# Dev-PCB.net
KiCad netlist of a schematic drawn in EAGLE
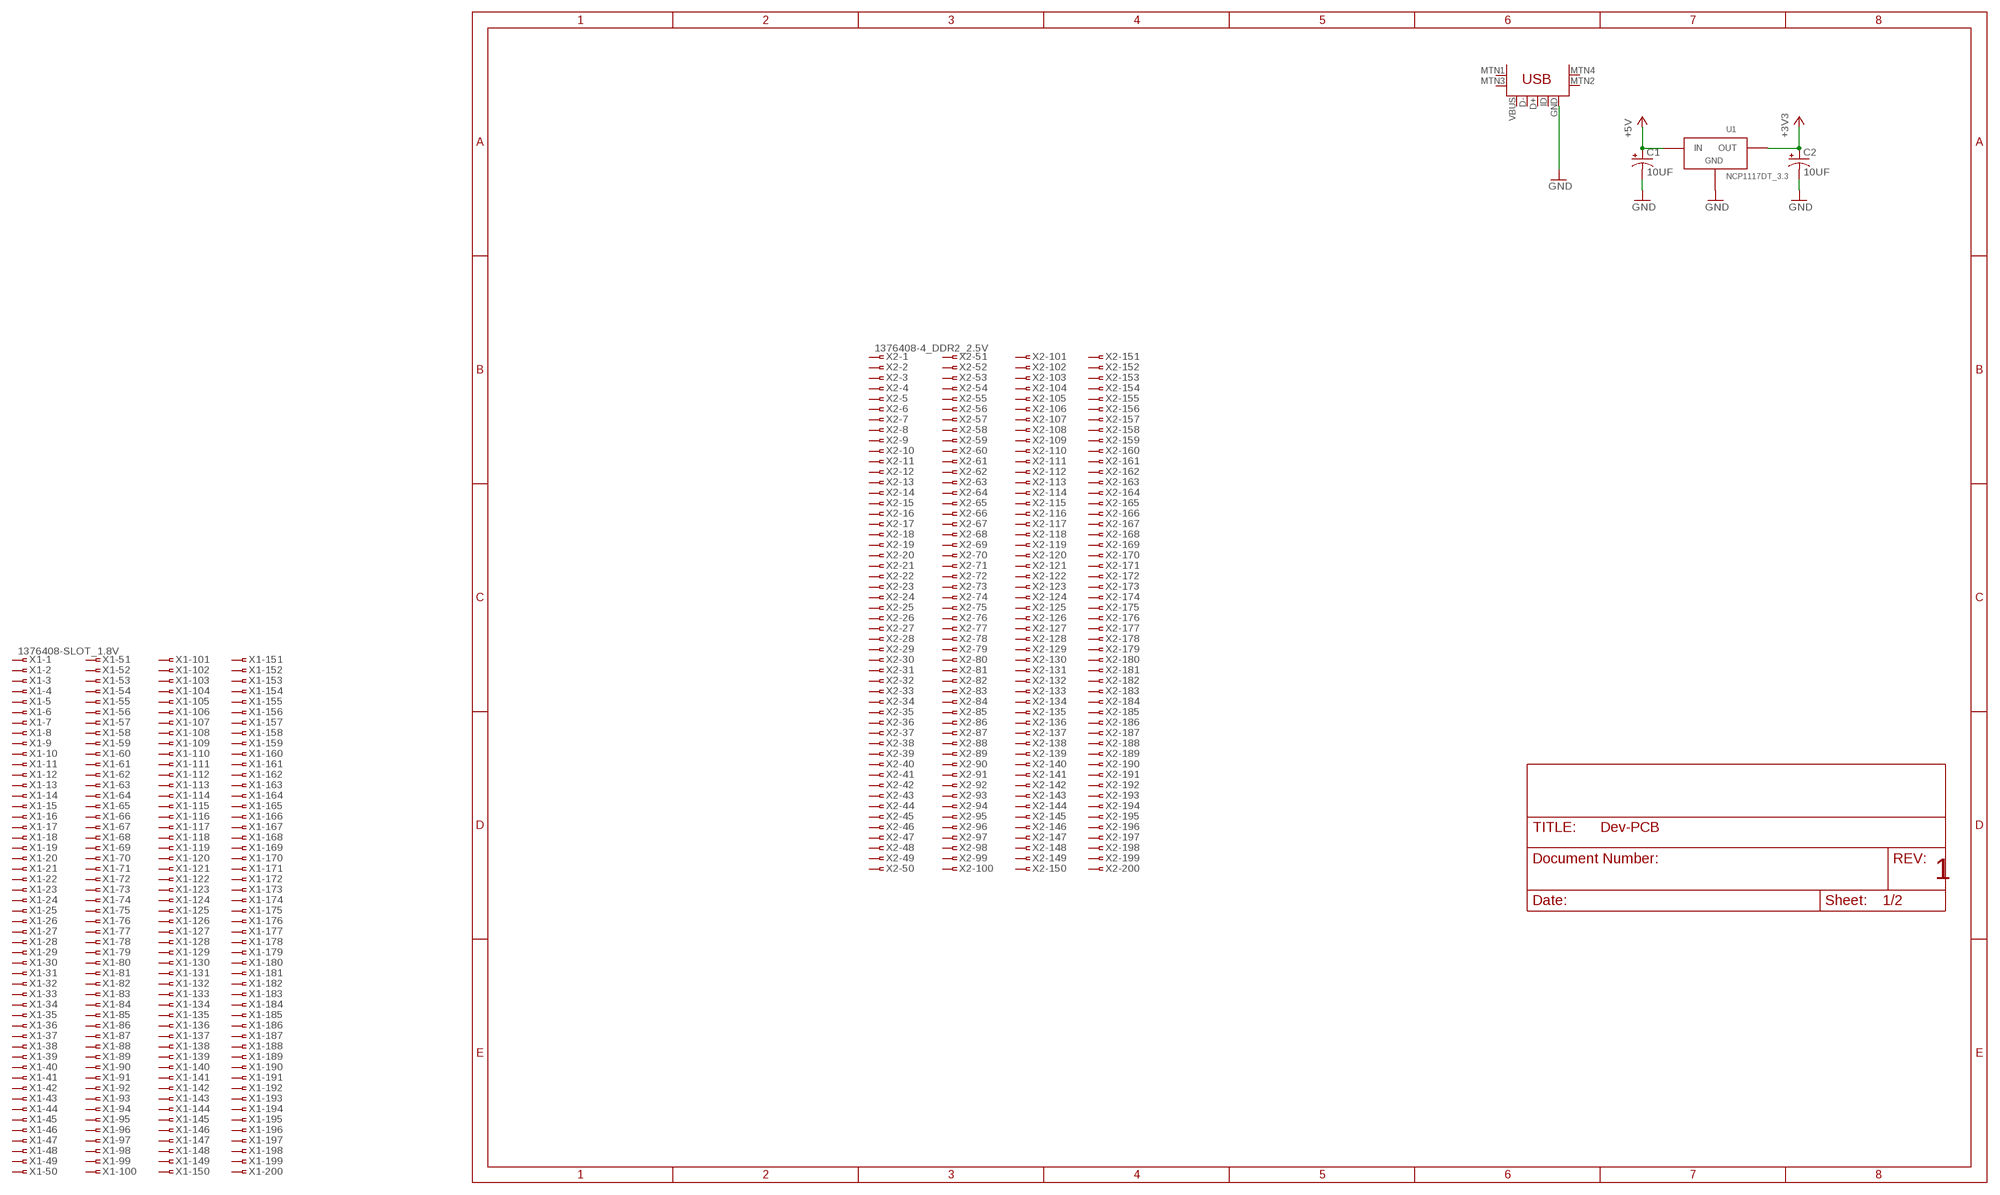
[diagram p0: schematic, sheet 1]

(export (version "E")
  (design (tool "Eeschema 10.0.6"))
  (components
    (comp (ref "C1")
      (value "10UF")
      (footprint "eagle-import:EIA3216-16V")
      (fields (field (name "PARTNO") "T491A106M016AT"))
      (libsource (lib "eagle-import") (part "CAP-POL_10UF_16V"))
    )
    (comp (ref "C2")
      (value "10UF")
      (footprint "eagle-import:EIA3216-16V")
      (fields (field (name "PARTNO") "T491A106M016AT"))
      (libsource (lib "eagle-import") (part "CAP-POL_10UF_16V"))
    )
    (comp (ref "U$1")
      (value "USB-MINIB-5PIN")
      (footprint "eagle-import:USB-MINIB")
      (libsource (lib "eagle-import") (part "USB-MINIB-5PIN"))
    )
    (comp (ref "U1")
      (value "NCP1117DT_3.3")
      (footprint "eagle-import:DPAK")
      (fields (field (name "PARTNO") "NCP1117DT33RKG"))
      (libsource (lib "eagle-import") (part "NCP1117DT_3.3"))
    )
    (comp (ref "X1")
      (value "1376408-SLOT_1.8V")
      (footprint "eagle-import:SLOT-1376408-1_1.8V")
      (libsource (lib "eagle-import") (part "1376408-SLOT_1.8V"))
    )
    (comp (ref "X2")
      (value "1376408-4_DDR2_2.5V")
      (footprint "eagle-import:1-1376408-4")
      (libsource (lib "eagle-import") (part "1376408-4_DDR2_2.5V"))
    )
  )
  (nets
    (net (code "1") (name "+3V3") (class "Default")
      (node (ref "C2") (pin "A") (pinfunction "+_A") (pintype "passive"))
      (node (ref "U1") (pin "2") (pinfunction "OUT_2") (pintype "bidirectional"))
    )
    (net (code "2") (name "+5V") (class "Default")
      (node (ref "C1") (pin "A") (pinfunction "+_A") (pintype "passive"))
      (node (ref "U1") (pin "3") (pinfunction "IN_3") (pintype "bidirectional"))
    )
    (net (code "3") (name "GND") (class "Default")
      (node (ref "C1") (pin "C") (pinfunction "+1_C") (pintype "passive"))
      (node (ref "C2") (pin "C") (pinfunction "+1_C") (pintype "passive"))
      (node (ref "U$1") (pin "GND") (pinfunction "GND_GND") (pintype "bidirectional"))
      (node (ref "U1") (pin "1") (pinfunction "GND_1") (pintype "bidirectional"))
    )
    (net (code "4") (name "unconnected-(U$1-MTN1-PadMTN3)") (class "Default")
      (node (ref "U$1") (pin "MTN3") (pinfunction "MTN1_MTN3") (pintype "bidirectional"))
    )
    (net (code "5") (name "unconnected-(U$1-MTN2-PadMTN1)") (class "Default")
      (node (ref "U$1") (pin "MTN1") (pinfunction "MTN2_MTN1") (pintype "bidirectional"))
    )
    (net (code "6") (name "unconnected-(U$1-MTN3-PadMTN2)") (class "Default")
      (node (ref "U$1") (pin "MTN2") (pinfunction "MTN3_MTN2") (pintype "bidirectional"))
    )
    (net (code "7") (name "unconnected-(U$1-PadD+)") (class "Default")
      (node (ref "U$1") (pin "D+") (pinfunction "D+_D+") (pintype "bidirectional"))
    )
    (net (code "8") (name "unconnected-(U$1-PadD-)") (class "Default")
      (node (ref "U$1") (pin "D-") (pinfunction "D-_D-") (pintype "bidirectional"))
    )
    (net (code "9") (name "unconnected-(U$1-PadID)") (class "Default")
      (node (ref "U$1") (pin "ID") (pinfunction "ID_ID") (pintype "bidirectional"))
    )
    (net (code "10") (name "unconnected-(U$1-PadMTN4)") (class "Default")
      (node (ref "U$1") (pin "MTN4") (pinfunction "MTN4_MTN4") (pintype "bidirectional"))
    )
    (net (code "11") (name "unconnected-(U$1-PadVBUS)") (class "Default")
      (node (ref "U$1") (pin "VBUS") (pinfunction "VBUS_VBUS") (pintype "bidirectional"))
    )
    (net (code "12") (name "unconnected-(X1-Pad1)") (class "Default")
      (node (ref "X1") (pin "1") (pinfunction "1_1") (pintype "passive"))
    )
    (net (code "13") (name "unconnected-(X1AA-1-Pad122)") (class "Default")
      (node (ref "X1") (pin "122") (pinfunction "1_122") (pintype "passive"))
    )
    (net (code "14") (name "unconnected-(X1AB-1-Pad123)") (class "Default")
      (node (ref "X1") (pin "123") (pinfunction "1_123") (pintype "passive"))
    )
    (net (code "15") (name "unconnected-(X1AC-1-Pad124)") (class "Default")
      (node (ref "X1") (pin "124") (pinfunction "1_124") (pintype "passive"))
    )
    (net (code "16") (name "unconnected-(X1AD-1-Pad125)") (class "Default")
      (node (ref "X1") (pin "125") (pinfunction "1_125") (pintype "passive"))
    )
    (net (code "17") (name "unconnected-(X1AE-1-Pad126)") (class "Default")
      (node (ref "X1") (pin "126") (pinfunction "1_126") (pintype "passive"))
    )
    (net (code "18") (name "unconnected-(X1AF-1-Pad127)") (class "Default")
      (node (ref "X1") (pin "127") (pinfunction "1_127") (pintype "passive"))
    )
    (net (code "19") (name "unconnected-(X1AG-1-Pad128)") (class "Default")
      (node (ref "X1") (pin "128") (pinfunction "1_128") (pintype "passive"))
    )
    (net (code "20") (name "unconnected-(X1AH-1-Pad129)") (class "Default")
      (node (ref "X1") (pin "129") (pinfunction "1_129") (pintype "passive"))
    )
    (net (code "21") (name "unconnected-(X1AI-1-Pad13)") (class "Default")
      (node (ref "X1") (pin "13") (pinfunction "1_13") (pintype "passive"))
    )
    (net (code "22") (name "unconnected-(X1AJ-1-Pad130)") (class "Default")
      (node (ref "X1") (pin "130") (pinfunction "1_130") (pintype "passive"))
    )
    (net (code "23") (name "unconnected-(X1AK-1-Pad131)") (class "Default")
      (node (ref "X1") (pin "131") (pinfunction "1_131") (pintype "passive"))
    )
    (net (code "24") (name "unconnected-(X1AL-1-Pad132)") (class "Default")
      (node (ref "X1") (pin "132") (pinfunction "1_132") (pintype "passive"))
    )
    (net (code "25") (name "unconnected-(X1AM-1-Pad133)") (class "Default")
      (node (ref "X1") (pin "133") (pinfunction "1_133") (pintype "passive"))
    )
    (net (code "26") (name "unconnected-(X1AN-1-Pad134)") (class "Default")
      (node (ref "X1") (pin "134") (pinfunction "1_134") (pintype "passive"))
    )
    (net (code "27") (name "unconnected-(X1AO-1-Pad135)") (class "Default")
      (node (ref "X1") (pin "135") (pinfunction "1_135") (pintype "passive"))
    )
    (net (code "28") (name "unconnected-(X1AP-1-Pad136)") (class "Default")
      (node (ref "X1") (pin "136") (pinfunction "1_136") (pintype "passive"))
    )
    (net (code "29") (name "unconnected-(X1AQ-1-Pad137)") (class "Default")
      (node (ref "X1") (pin "137") (pinfunction "1_137") (pintype "passive"))
    )
    (net (code "30") (name "unconnected-(X1AR-1-Pad138)") (class "Default")
      (node (ref "X1") (pin "138") (pinfunction "1_138") (pintype "passive"))
    )
    (net (code "31") (name "unconnected-(X1AS-1-Pad139)") (class "Default")
      (node (ref "X1") (pin "139") (pinfunction "1_139") (pintype "passive"))
    )
    (net (code "32") (name "unconnected-(X1AT-1-Pad14)") (class "Default")
      (node (ref "X1") (pin "14") (pinfunction "1_14") (pintype "passive"))
    )
    (net (code "33") (name "unconnected-(X1AU-1-Pad140)") (class "Default")
      (node (ref "X1") (pin "140") (pinfunction "1_140") (pintype "passive"))
    )
    (net (code "34") (name "unconnected-(X1AV-1-Pad141)") (class "Default")
      (node (ref "X1") (pin "141") (pinfunction "1_141") (pintype "passive"))
    )
    (net (code "35") (name "unconnected-(X1AW-1-Pad142)") (class "Default")
      (node (ref "X1") (pin "142") (pinfunction "1_142") (pintype "passive"))
    )
    (net (code "36") (name "unconnected-(X1AX-1-Pad143)") (class "Default")
      (node (ref "X1") (pin "143") (pinfunction "1_143") (pintype "passive"))
    )
    (net (code "37") (name "unconnected-(X1AY-1-Pad144)") (class "Default")
      (node (ref "X1") (pin "144") (pinfunction "1_144") (pintype "passive"))
    )
    (net (code "38") (name "unconnected-(X1AZ-1-Pad145)") (class "Default")
      (node (ref "X1") (pin "145") (pinfunction "1_145") (pintype "passive"))
    )
    (net (code "39") (name "unconnected-(X1B-1-Pad10)") (class "Default")
      (node (ref "X1") (pin "10") (pinfunction "1_10") (pintype "passive"))
    )
    (net (code "40") (name "unconnected-(X1BA-1-Pad146)") (class "Default")
      (node (ref "X1") (pin "146") (pinfunction "1_146") (pintype "passive"))
    )
    (net (code "41") (name "unconnected-(X1BB-1-Pad147)") (class "Default")
      (node (ref "X1") (pin "147") (pinfunction "1_147") (pintype "passive"))
    )
    (net (code "42") (name "unconnected-(X1BC-1-Pad148)") (class "Default")
      (node (ref "X1") (pin "148") (pinfunction "1_148") (pintype "passive"))
    )
    (net (code "43") (name "unconnected-(X1BD-1-Pad149)") (class "Default")
      (node (ref "X1") (pin "149") (pinfunction "1_149") (pintype "passive"))
    )
    (net (code "44") (name "unconnected-(X1BE-1-Pad15)") (class "Default")
      (node (ref "X1") (pin "15") (pinfunction "1_15") (pintype "passive"))
    )
    (net (code "45") (name "unconnected-(X1BF-1-Pad150)") (class "Default")
      (node (ref "X1") (pin "150") (pinfunction "1_150") (pintype "passive"))
    )
    (net (code "46") (name "unconnected-(X1BG-1-Pad151)") (class "Default")
      (node (ref "X1") (pin "151") (pinfunction "1_151") (pintype "passive"))
    )
    (net (code "47") (name "unconnected-(X1BH-1-Pad152)") (class "Default")
      (node (ref "X1") (pin "152") (pinfunction "1_152") (pintype "passive"))
    )
    (net (code "48") (name "unconnected-(X1BI-1-Pad153)") (class "Default")
      (node (ref "X1") (pin "153") (pinfunction "1_153") (pintype "passive"))
    )
    (net (code "49") (name "unconnected-(X1BJ-1-Pad154)") (class "Default")
      (node (ref "X1") (pin "154") (pinfunction "1_154") (pintype "passive"))
    )
    (net (code "50") (name "unconnected-(X1BK-1-Pad155)") (class "Default")
      (node (ref "X1") (pin "155") (pinfunction "1_155") (pintype "passive"))
    )
    (net (code "51") (name "unconnected-(X1BL-1-Pad156)") (class "Default")
      (node (ref "X1") (pin "156") (pinfunction "1_156") (pintype "passive"))
    )
    (net (code "52") (name "unconnected-(X1BM-1-Pad157)") (class "Default")
      (node (ref "X1") (pin "157") (pinfunction "1_157") (pintype "passive"))
    )
    (net (code "53") (name "unconnected-(X1BN-1-Pad158)") (class "Default")
      (node (ref "X1") (pin "158") (pinfunction "1_158") (pintype "passive"))
    )
    (net (code "54") (name "unconnected-(X1BO-1-Pad159)") (class "Default")
      (node (ref "X1") (pin "159") (pinfunction "1_159") (pintype "passive"))
    )
    (net (code "55") (name "unconnected-(X1BP-1-Pad16)") (class "Default")
      (node (ref "X1") (pin "16") (pinfunction "1_16") (pintype "passive"))
    )
    (net (code "56") (name "unconnected-(X1BQ-1-Pad160)") (class "Default")
      (node (ref "X1") (pin "160") (pinfunction "1_160") (pintype "passive"))
    )
    (net (code "57") (name "unconnected-(X1BR-1-Pad161)") (class "Default")
      (node (ref "X1") (pin "161") (pinfunction "1_161") (pintype "passive"))
    )
    (net (code "58") (name "unconnected-(X1BS-1-Pad162)") (class "Default")
      (node (ref "X1") (pin "162") (pinfunction "1_162") (pintype "passive"))
    )
    (net (code "59") (name "unconnected-(X1BT-1-Pad163)") (class "Default")
      (node (ref "X1") (pin "163") (pinfunction "1_163") (pintype "passive"))
    )
    (net (code "60") (name "unconnected-(X1BU-1-Pad164)") (class "Default")
      (node (ref "X1") (pin "164") (pinfunction "1_164") (pintype "passive"))
    )
    (net (code "61") (name "unconnected-(X1BV-1-Pad165)") (class "Default")
      (node (ref "X1") (pin "165") (pinfunction "1_165") (pintype "passive"))
    )
    (net (code "62") (name "unconnected-(X1BW-1-Pad166)") (class "Default")
      (node (ref "X1") (pin "166") (pinfunction "1_166") (pintype "passive"))
    )
    (net (code "63") (name "unconnected-(X1BX-1-Pad167)") (class "Default")
      (node (ref "X1") (pin "167") (pinfunction "1_167") (pintype "passive"))
    )
    (net (code "64") (name "unconnected-(X1BY-1-Pad168)") (class "Default")
      (node (ref "X1") (pin "168") (pinfunction "1_168") (pintype "passive"))
    )
    (net (code "65") (name "unconnected-(X1BZ-1-Pad169)") (class "Default")
      (node (ref "X1") (pin "169") (pinfunction "1_169") (pintype "passive"))
    )
    (net (code "66") (name "unconnected-(X1C-1-Pad100)") (class "Default")
      (node (ref "X1") (pin "100") (pinfunction "1_100") (pintype "passive"))
    )
    (net (code "67") (name "unconnected-(X1CA-1-Pad17)") (class "Default")
      (node (ref "X1") (pin "17") (pinfunction "1_17") (pintype "passive"))
    )
    (net (code "68") (name "unconnected-(X1CB-1-Pad170)") (class "Default")
      (node (ref "X1") (pin "170") (pinfunction "1_170") (pintype "passive"))
    )
    (net (code "69") (name "unconnected-(X1CC-1-Pad171)") (class "Default")
      (node (ref "X1") (pin "171") (pinfunction "1_171") (pintype "passive"))
    )
    (net (code "70") (name "unconnected-(X1CD-1-Pad172)") (class "Default")
      (node (ref "X1") (pin "172") (pinfunction "1_172") (pintype "passive"))
    )
    (net (code "71") (name "unconnected-(X1CE-1-Pad173)") (class "Default")
      (node (ref "X1") (pin "173") (pinfunction "1_173") (pintype "passive"))
    )
    (net (code "72") (name "unconnected-(X1CF-1-Pad174)") (class "Default")
      (node (ref "X1") (pin "174") (pinfunction "1_174") (pintype "passive"))
    )
    (net (code "73") (name "unconnected-(X1CG-1-Pad175)") (class "Default")
      (node (ref "X1") (pin "175") (pinfunction "1_175") (pintype "passive"))
    )
    (net (code "74") (name "unconnected-(X1CH-1-Pad176)") (class "Default")
      (node (ref "X1") (pin "176") (pinfunction "1_176") (pintype "passive"))
    )
    (net (code "75") (name "unconnected-(X1CI-1-Pad177)") (class "Default")
      (node (ref "X1") (pin "177") (pinfunction "1_177") (pintype "passive"))
    )
    (net (code "76") (name "unconnected-(X1CJ-1-Pad178)") (class "Default")
      (node (ref "X1") (pin "178") (pinfunction "1_178") (pintype "passive"))
    )
    (net (code "77") (name "unconnected-(X1CK-1-Pad179)") (class "Default")
      (node (ref "X1") (pin "179") (pinfunction "1_179") (pintype "passive"))
    )
    (net (code "78") (name "unconnected-(X1CL-1-Pad18)") (class "Default")
      (node (ref "X1") (pin "18") (pinfunction "1_18") (pintype "passive"))
    )
    (net (code "79") (name "unconnected-(X1CM-1-Pad180)") (class "Default")
      (node (ref "X1") (pin "180") (pinfunction "1_180") (pintype "passive"))
    )
    (net (code "80") (name "unconnected-(X1CN-1-Pad181)") (class "Default")
      (node (ref "X1") (pin "181") (pinfunction "1_181") (pintype "passive"))
    )
    (net (code "81") (name "unconnected-(X1CO-1-Pad182)") (class "Default")
      (node (ref "X1") (pin "182") (pinfunction "1_182") (pintype "passive"))
    )
    (net (code "82") (name "unconnected-(X1CP-1-Pad183)") (class "Default")
      (node (ref "X1") (pin "183") (pinfunction "1_183") (pintype "passive"))
    )
    (net (code "83") (name "unconnected-(X1CQ-1-Pad184)") (class "Default")
      (node (ref "X1") (pin "184") (pinfunction "1_184") (pintype "passive"))
    )
    (net (code "84") (name "unconnected-(X1CR-1-Pad185)") (class "Default")
      (node (ref "X1") (pin "185") (pinfunction "1_185") (pintype "passive"))
    )
    (net (code "85") (name "unconnected-(X1CS-1-Pad186)") (class "Default")
      (node (ref "X1") (pin "186") (pinfunction "1_186") (pintype "passive"))
    )
    (net (code "86") (name "unconnected-(X1CT-1-Pad187)") (class "Default")
      (node (ref "X1") (pin "187") (pinfunction "1_187") (pintype "passive"))
    )
    (net (code "87") (name "unconnected-(X1CU-1-Pad188)") (class "Default")
      (node (ref "X1") (pin "188") (pinfunction "1_188") (pintype "passive"))
    )
    (net (code "88") (name "unconnected-(X1CV-1-Pad189)") (class "Default")
      (node (ref "X1") (pin "189") (pinfunction "1_189") (pintype "passive"))
    )
    (net (code "89") (name "unconnected-(X1CW-1-Pad19)") (class "Default")
      (node (ref "X1") (pin "19") (pinfunction "1_19") (pintype "passive"))
    )
    (net (code "90") (name "unconnected-(X1CX-1-Pad190)") (class "Default")
      (node (ref "X1") (pin "190") (pinfunction "1_190") (pintype "passive"))
    )
    (net (code "91") (name "unconnected-(X1CY-1-Pad191)") (class "Default")
      (node (ref "X1") (pin "191") (pinfunction "1_191") (pintype "passive"))
    )
    (net (code "92") (name "unconnected-(X1CZ-1-Pad192)") (class "Default")
      (node (ref "X1") (pin "192") (pinfunction "1_192") (pintype "passive"))
    )
    (net (code "93") (name "unconnected-(X1D-1-Pad101)") (class "Default")
      (node (ref "X1") (pin "101") (pinfunction "1_101") (pintype "passive"))
    )
    (net (code "94") (name "unconnected-(X1DA-1-Pad193)") (class "Default")
      (node (ref "X1") (pin "193") (pinfunction "1_193") (pintype "passive"))
    )
    (net (code "95") (name "unconnected-(X1DB-1-Pad194)") (class "Default")
      (node (ref "X1") (pin "194") (pinfunction "1_194") (pintype "passive"))
    )
    (net (code "96") (name "unconnected-(X1DC-1-Pad195)") (class "Default")
      (node (ref "X1") (pin "195") (pinfunction "1_195") (pintype "passive"))
    )
    (net (code "97") (name "unconnected-(X1DD-1-Pad196)") (class "Default")
      (node (ref "X1") (pin "196") (pinfunction "1_196") (pintype "passive"))
    )
    (net (code "98") (name "unconnected-(X1DE-1-Pad197)") (class "Default")
      (node (ref "X1") (pin "197") (pinfunction "1_197") (pintype "passive"))
    )
    (net (code "99") (name "unconnected-(X1DF-1-Pad198)") (class "Default")
      (node (ref "X1") (pin "198") (pinfunction "1_198") (pintype "passive"))
    )
    (net (code "100") (name "unconnected-(X1DG-1-Pad199)") (class "Default")
      (node (ref "X1") (pin "199") (pinfunction "1_199") (pintype "passive"))
    )
    (net (code "101") (name "unconnected-(X1DH-1-Pad2)") (class "Default")
      (node (ref "X1") (pin "2") (pinfunction "1_2") (pintype "passive"))
    )
    (net (code "102") (name "unconnected-(X1DI-1-Pad20)") (class "Default")
      (node (ref "X1") (pin "20") (pinfunction "1_20") (pintype "passive"))
    )
    (net (code "103") (name "unconnected-(X1DJ-1-Pad200)") (class "Default")
      (node (ref "X1") (pin "200") (pinfunction "1_200") (pintype "passive"))
    )
    (net (code "104") (name "unconnected-(X1DK-1-Pad21)") (class "Default")
      (node (ref "X1") (pin "21") (pinfunction "1_21") (pintype "passive"))
    )
    (net (code "105") (name "unconnected-(X1DL-1-Pad22)") (class "Default")
      (node (ref "X1") (pin "22") (pinfunction "1_22") (pintype "passive"))
    )
    (net (code "106") (name "unconnected-(X1DM-1-Pad23)") (class "Default")
      (node (ref "X1") (pin "23") (pinfunction "1_23") (pintype "passive"))
    )
    (net (code "107") (name "unconnected-(X1DN-1-Pad24)") (class "Default")
      (node (ref "X1") (pin "24") (pinfunction "1_24") (pintype "passive"))
    )
    (net (code "108") (name "unconnected-(X1DO-1-Pad25)") (class "Default")
      (node (ref "X1") (pin "25") (pinfunction "1_25") (pintype "passive"))
    )
    (net (code "109") (name "unconnected-(X1DP-1-Pad26)") (class "Default")
      (node (ref "X1") (pin "26") (pinfunction "1_26") (pintype "passive"))
    )
    (net (code "110") (name "unconnected-(X1DQ-1-Pad27)") (class "Default")
      (node (ref "X1") (pin "27") (pinfunction "1_27") (pintype "passive"))
    )
    (net (code "111") (name "unconnected-(X1DR-1-Pad28)") (class "Default")
      (node (ref "X1") (pin "28") (pinfunction "1_28") (pintype "passive"))
    )
    (net (code "112") (name "unconnected-(X1DS-1-Pad29)") (class "Default")
      (node (ref "X1") (pin "29") (pinfunction "1_29") (pintype "passive"))
    )
    (net (code "113") (name "unconnected-(X1DT-1-Pad3)") (class "Default")
      (node (ref "X1") (pin "3") (pinfunction "1_3") (pintype "passive"))
    )
    (net (code "114") (name "unconnected-(X1DU-1-Pad30)") (class "Default")
      (node (ref "X1") (pin "30") (pinfunction "1_30") (pintype "passive"))
    )
    (net (code "115") (name "unconnected-(X1DV-1-Pad31)") (class "Default")
      (node (ref "X1") (pin "31") (pinfunction "1_31") (pintype "passive"))
    )
    (net (code "116") (name "unconnected-(X1DW-1-Pad32)") (class "Default")
      (node (ref "X1") (pin "32") (pinfunction "1_32") (pintype "passive"))
    )
    (net (code "117") (name "unconnected-(X1DX-1-Pad33)") (class "Default")
      (node (ref "X1") (pin "33") (pinfunction "1_33") (pintype "passive"))
    )
    (net (code "118") (name "unconnected-(X1DY-1-Pad34)") (class "Default")
      (node (ref "X1") (pin "34") (pinfunction "1_34") (pintype "passive"))
    )
    (net (code "119") (name "unconnected-(X1DZ-1-Pad35)") (class "Default")
      (node (ref "X1") (pin "35") (pinfunction "1_35") (pintype "passive"))
    )
    (net (code "120") (name "unconnected-(X1E-1-Pad102)") (class "Default")
      (node (ref "X1") (pin "102") (pinfunction "1_102") (pintype "passive"))
    )
    (net (code "121") (name "unconnected-(X1EA-1-Pad36)") (class "Default")
      (node (ref "X1") (pin "36") (pinfunction "1_36") (pintype "passive"))
    )
    (net (code "122") (name "unconnected-(X1EB-1-Pad37)") (class "Default")
      (node (ref "X1") (pin "37") (pinfunction "1_37") (pintype "passive"))
    )
    (net (code "123") (name "unconnected-(X1EC-1-Pad38)") (class "Default")
      (node (ref "X1") (pin "38") (pinfunction "1_38") (pintype "passive"))
    )
    (net (code "124") (name "unconnected-(X1ED-1-Pad39)") (class "Default")
      (node (ref "X1") (pin "39") (pinfunction "1_39") (pintype "passive"))
    )
    (net (code "125") (name "unconnected-(X1EE-1-Pad4)") (class "Default")
      (node (ref "X1") (pin "4") (pinfunction "1_4") (pintype "passive"))
    )
    (net (code "126") (name "unconnected-(X1EF-1-Pad40)") (class "Default")
      (node (ref "X1") (pin "40") (pinfunction "1_40") (pintype "passive"))
    )
    (net (code "127") (name "unconnected-(X1EG-1-Pad41)") (class "Default")
      (node (ref "X1") (pin "41") (pinfunction "1_41") (pintype "passive"))
    )
    (net (code "128") (name "unconnected-(X1EH-1-Pad42)") (class "Default")
      (node (ref "X1") (pin "42") (pinfunction "1_42") (pintype "passive"))
    )
    (net (code "129") (name "unconnected-(X1EI-1-Pad43)") (class "Default")
      (node (ref "X1") (pin "43") (pinfunction "1_43") (pintype "passive"))
    )
    (net (code "130") (name "unconnected-(X1EJ-1-Pad44)") (class "Default")
      (node (ref "X1") (pin "44") (pinfunction "1_44") (pintype "passive"))
    )
    (net (code "131") (name "unconnected-(X1EK-1-Pad45)") (class "Default")
      (node (ref "X1") (pin "45") (pinfunction "1_45") (pintype "passive"))
    )
    (net (code "132") (name "unconnected-(X1EL-1-Pad46)") (class "Default")
      (node (ref "X1") (pin "46") (pinfunction "1_46") (pintype "passive"))
    )
    (net (code "133") (name "unconnected-(X1EM-1-Pad47)") (class "Default")
      (node (ref "X1") (pin "47") (pinfunction "1_47") (pintype "passive"))
    )
    (net (code "134") (name "unconnected-(X1EN-1-Pad48)") (class "Default")
      (node (ref "X1") (pin "48") (pinfunction "1_48") (pintype "passive"))
    )
    (net (code "135") (name "unconnected-(X1EO-1-Pad49)") (class "Default")
      (node (ref "X1") (pin "49") (pinfunction "1_49") (pintype "passive"))
    )
    (net (code "136") (name "unconnected-(X1EP-1-Pad5)") (class "Default")
      (node (ref "X1") (pin "5") (pinfunction "1_5") (pintype "passive"))
    )
    (net (code "137") (name "unconnected-(X1EQ-1-Pad50)") (class "Default")
      (node (ref "X1") (pin "50") (pinfunction "1_50") (pintype "passive"))
    )
    (net (code "138") (name "unconnected-(X1ER-1-Pad51)") (class "Default")
      (node (ref "X1") (pin "51") (pinfunction "1_51") (pintype "passive"))
    )
    (net (code "139") (name "unconnected-(X1ES-1-Pad52)") (class "Default")
      (node (ref "X1") (pin "52") (pinfunction "1_52") (pintype "passive"))
    )
    (net (code "140") (name "unconnected-(X1ET-1-Pad53)") (class "Default")
      (node (ref "X1") (pin "53") (pinfunction "1_53") (pintype "passive"))
    )
    (net (code "141") (name "unconnected-(X1EU-1-Pad54)") (class "Default")
      (node (ref "X1") (pin "54") (pinfunction "1_54") (pintype "passive"))
    )
    (net (code "142") (name "unconnected-(X1EV-1-Pad55)") (class "Default")
      (node (ref "X1") (pin "55") (pinfunction "1_55") (pintype "passive"))
    )
    (net (code "143") (name "unconnected-(X1EW-1-Pad56)") (class "Default")
      (node (ref "X1") (pin "56") (pinfunction "1_56") (pintype "passive"))
    )
    (net (code "144") (name "unconnected-(X1EX-1-Pad57)") (class "Default")
      (node (ref "X1") (pin "57") (pinfunction "1_57") (pintype "passive"))
    )
    (net (code "145") (name "unconnected-(X1EY-1-Pad58)") (class "Default")
      (node (ref "X1") (pin "58") (pinfunction "1_58") (pintype "passive"))
    )
    (net (code "146") (name "unconnected-(X1EZ-1-Pad59)") (class "Default")
      (node (ref "X1") (pin "59") (pinfunction "1_59") (pintype "passive"))
    )
    (net (code "147") (name "unconnected-(X1F-1-Pad103)") (class "Default")
      (node (ref "X1") (pin "103") (pinfunction "1_103") (pintype "passive"))
    )
    (net (code "148") (name "unconnected-(X1FA-1-Pad6)") (class "Default")
      (node (ref "X1") (pin "6") (pinfunction "1_6") (pintype "passive"))
    )
    (net (code "149") (name "unconnected-(X1FB-1-Pad60)") (class "Default")
      (node (ref "X1") (pin "60") (pinfunction "1_60") (pintype "passive"))
    )
    (net (code "150") (name "unconnected-(X1FC-1-Pad61)") (class "Default")
      (node (ref "X1") (pin "61") (pinfunction "1_61") (pintype "passive"))
    )
    (net (code "151") (name "unconnected-(X1FD-1-Pad62)") (class "Default")
      (node (ref "X1") (pin "62") (pinfunction "1_62") (pintype "passive"))
    )
    (net (code "152") (name "unconnected-(X1FE-1-Pad63)") (class "Default")
      (node (ref "X1") (pin "63") (pinfunction "1_63") (pintype "passive"))
    )
    (net (code "153") (name "unconnected-(X1FF-1-Pad64)") (class "Default")
      (node (ref "X1") (pin "64") (pinfunction "1_64") (pintype "passive"))
    )
    (net (code "154") (name "unconnected-(X1FG-1-Pad65)") (class "Default")
      (node (ref "X1") (pin "65") (pinfunction "1_65") (pintype "passive"))
    )
    (net (code "155") (name "unconnected-(X1FH-1-Pad66)") (class "Default")
      (node (ref "X1") (pin "66") (pinfunction "1_66") (pintype "passive"))
    )
    (net (code "156") (name "unconnected-(X1FI-1-Pad67)") (class "Default")
      (node (ref "X1") (pin "67") (pinfunction "1_67") (pintype "passive"))
    )
    (net (code "157") (name "unconnected-(X1FJ-1-Pad68)") (class "Default")
      (node (ref "X1") (pin "68") (pinfunction "1_68") (pintype "passive"))
    )
    (net (code "158") (name "unconnected-(X1FK-1-Pad69)") (class "Default")
      (node (ref "X1") (pin "69") (pinfunction "1_69") (pintype "passive"))
    )
    (net (code "159") (name "unconnected-(X1FL-1-Pad7)") (class "Default")
      (node (ref "X1") (pin "7") (pinfunction "1_7") (pintype "passive"))
    )
    (net (code "160") (name "unconnected-(X1FM-1-Pad70)") (class "Default")
      (node (ref "X1") (pin "70") (pinfunction "1_70") (pintype "passive"))
    )
    (net (code "161") (name "unconnected-(X1FN-1-Pad71)") (class "Default")
      (node (ref "X1") (pin "71") (pinfunction "1_71") (pintype "passive"))
    )
    (net (code "162") (name "unconnected-(X1FO-1-Pad72)") (class "Default")
      (node (ref "X1") (pin "72") (pinfunction "1_72") (pintype "passive"))
    )
    (net (code "163") (name "unconnected-(X1FP-1-Pad73)") (class "Default")
      (node (ref "X1") (pin "73") (pinfunction "1_73") (pintype "passive"))
    )
    (net (code "164") (name "unconnected-(X1FQ-1-Pad74)") (class "Default")
      (node (ref "X1") (pin "74") (pinfunction "1_74") (pintype "passive"))
    )
    (net (code "165") (name "unconnected-(X1FR-1-Pad75)") (class "Default")
      (node (ref "X1") (pin "75") (pinfunction "1_75") (pintype "passive"))
    )
    (net (code "166") (name "unconnected-(X1FS-1-Pad76)") (class "Default")
      (node (ref "X1") (pin "76") (pinfunction "1_76") (pintype "passive"))
    )
    (net (code "167") (name "unconnected-(X1FT-1-Pad77)") (class "Default")
      (node (ref "X1") (pin "77") (pinfunction "1_77") (pintype "passive"))
    )
    (net (code "168") (name "unconnected-(X1FU-1-Pad78)") (class "Default")
      (node (ref "X1") (pin "78") (pinfunction "1_78") (pintype "passive"))
    )
    (net (code "169") (name "unconnected-(X1FV-1-Pad79)") (class "Default")
      (node (ref "X1") (pin "79") (pinfunction "1_79") (pintype "passive"))
    )
    (net (code "170") (name "unconnected-(X1FW-1-Pad8)") (class "Default")
      (node (ref "X1") (pin "8") (pinfunction "1_8") (pintype "passive"))
    )
    (net (code "171") (name "unconnected-(X1FX-1-Pad80)") (class "Default")
      (node (ref "X1") (pin "80") (pinfunction "1_80") (pintype "passive"))
    )
    (net (code "172") (name "unconnected-(X1FY-1-Pad81)") (class "Default")
      (node (ref "X1") (pin "81") (pinfunction "1_81") (pintype "passive"))
    )
    (net (code "173") (name "unconnected-(X1FZ-1-Pad82)") (class "Default")
      (node (ref "X1") (pin "82") (pinfunction "1_82") (pintype "passive"))
    )
    (net (code "174") (name "unconnected-(X1G-1-Pad104)") (class "Default")
      (node (ref "X1") (pin "104") (pinfunction "1_104") (pintype "passive"))
    )
    (net (code "175") (name "unconnected-(X1GA-1-Pad83)") (class "Default")
      (node (ref "X1") (pin "83") (pinfunction "1_83") (pintype "passive"))
    )
    (net (code "176") (name "unconnected-(X1GB-1-Pad84)") (class "Default")
      (node (ref "X1") (pin "84") (pinfunction "1_84") (pintype "passive"))
    )
    (net (code "177") (name "unconnected-(X1GC-1-Pad85)") (class "Default")
      (node (ref "X1") (pin "85") (pinfunction "1_85") (pintype "passive"))
    )
    (net (code "178") (name "unconnected-(X1GD-1-Pad86)") (class "Default")
      (node (ref "X1") (pin "86") (pinfunction "1_86") (pintype "passive"))
    )
    (net (code "179") (name "unconnected-(X1GE-1-Pad87)") (class "Default")
      (node (ref "X1") (pin "87") (pinfunction "1_87") (pintype "passive"))
    )
    (net (code "180") (name "unconnected-(X1GF-1-Pad88)") (class "Default")
      (node (ref "X1") (pin "88") (pinfunction "1_88") (pintype "passive"))
    )
    (net (code "181") (name "unconnected-(X1GG-1-Pad89)") (class "Default")
      (node (ref "X1") (pin "89") (pinfunction "1_89") (pintype "passive"))
    )
    (net (code "182") (name "unconnected-(X1GH-1-Pad9)") (class "Default")
      (node (ref "X1") (pin "9") (pinfunction "1_9") (pintype "passive"))
    )
    (net (code "183") (name "unconnected-(X1GI-1-Pad90)") (class "Default")
      (node (ref "X1") (pin "90") (pinfunction "1_90") (pintype "passive"))
    )
    (net (code "184") (name "unconnected-(X1GJ-1-Pad91)") (class "Default")
      (node (ref "X1") (pin "91") (pinfunction "1_91") (pintype "passive"))
    )
    (net (code "185") (name "unconnected-(X1GK-1-Pad92)") (class "Default")
      (node (ref "X1") (pin "92") (pinfunction "1_92") (pintype "passive"))
    )
    (net (code "186") (name "unconnected-(X1GL-1-Pad93)") (class "Default")
      (node (ref "X1") (pin "93") (pinfunction "1_93") (pintype "passive"))
    )
    (net (code "187") (name "unconnected-(X1GM-1-Pad94)") (class "Default")
      (node (ref "X1") (pin "94") (pinfunction "1_94") (pintype "passive"))
    )
    (net (code "188") (name "unconnected-(X1GN-1-Pad95)") (class "Default")
      (node (ref "X1") (pin "95") (pinfunction "1_95") (pintype "passive"))
    )
    (net (code "189") (name "unconnected-(X1GO-1-Pad96)") (class "Default")
      (node (ref "X1") (pin "96") (pinfunction "1_96") (pintype "passive"))
    )
    (net (code "190") (name "unconnected-(X1GP-1-Pad97)") (class "Default")
      (node (ref "X1") (pin "97") (pinfunction "1_97") (pintype "passive"))
    )
    (net (code "191") (name "unconnected-(X1GQ-1-Pad98)") (class "Default")
      (node (ref "X1") (pin "98") (pinfunction "1_98") (pintype "passive"))
    )
    (net (code "192") (name "unconnected-(X1GR-1-Pad99)") (class "Default")
      (node (ref "X1") (pin "99") (pinfunction "1_99") (pintype "passive"))
    )
    (net (code "193") (name "unconnected-(X1H-1-Pad105)") (class "Default")
      (node (ref "X1") (pin "105") (pinfunction "1_105") (pintype "passive"))
    )
    (net (code "194") (name "unconnected-(X1I-1-Pad106)") (class "Default")
      (node (ref "X1") (pin "106") (pinfunction "1_106") (pintype "passive"))
    )
    (net (code "195") (name "unconnected-(X1J-1-Pad107)") (class "Default")
      (node (ref "X1") (pin "107") (pinfunction "1_107") (pintype "passive"))
    )
    (net (code "196") (name "unconnected-(X1K-1-Pad108)") (class "Default")
      (node (ref "X1") (pin "108") (pinfunction "1_108") (pintype "passive"))
    )
    (net (code "197") (name "unconnected-(X1L-1-Pad109)") (class "Default")
      (node (ref "X1") (pin "109") (pinfunction "1_109") (pintype "passive"))
    )
    (net (code "198") (name "unconnected-(X1M-1-Pad11)") (class "Default")
      (node (ref "X1") (pin "11") (pinfunction "1_11") (pintype "passive"))
    )
    (net (code "199") (name "unconnected-(X1N-1-Pad110)") (class "Default")
      (node (ref "X1") (pin "110") (pinfunction "1_110") (pintype "passive"))
    )
    (net (code "200") (name "unconnected-(X1O-1-Pad111)") (class "Default")
      (node (ref "X1") (pin "111") (pinfunction "1_111") (pintype "passive"))
    )
    (net (code "201") (name "unconnected-(X1P-1-Pad112)") (class "Default")
      (node (ref "X1") (pin "112") (pinfunction "1_112") (pintype "passive"))
    )
    (net (code "202") (name "unconnected-(X1Q-1-Pad113)") (class "Default")
      (node (ref "X1") (pin "113") (pinfunction "1_113") (pintype "passive"))
    )
    (net (code "203") (name "unconnected-(X1R-1-Pad114)") (class "Default")
      (node (ref "X1") (pin "114") (pinfunction "1_114") (pintype "passive"))
    )
    (net (code "204") (name "unconnected-(X1S-1-Pad115)") (class "Default")
      (node (ref "X1") (pin "115") (pinfunction "1_115") (pintype "passive"))
    )
    (net (code "205") (name "unconnected-(X1T-1-Pad116)") (class "Default")
      (node (ref "X1") (pin "116") (pinfunction "1_116") (pintype "passive"))
    )
    (net (code "206") (name "unconnected-(X1U-1-Pad117)") (class "Default")
      (node (ref "X1") (pin "117") (pinfunction "1_117") (pintype "passive"))
    )
    (net (code "207") (name "unconnected-(X1V-1-Pad118)") (class "Default")
      (node (ref "X1") (pin "118") (pinfunction "1_118") (pintype "passive"))
    )
    (net (code "208") (name "unconnected-(X1W-1-Pad119)") (class "Default")
      (node (ref "X1") (pin "119") (pinfunction "1_119") (pintype "passive"))
    )
    (net (code "209") (name "unconnected-(X1X-1-Pad12)") (class "Default")
      (node (ref "X1") (pin "12") (pinfunction "1_12") (pintype "passive"))
    )
    (net (code "210") (name "unconnected-(X1Y-1-Pad120)") (class "Default")
      (node (ref "X1") (pin "120") (pinfunction "1_120") (pintype "passive"))
    )
    (net (code "211") (name "unconnected-(X1Z-1-Pad121)") (class "Default")
      (node (ref "X1") (pin "121") (pinfunction "1_121") (pintype "passive"))
    )
    (net (code "212") (name "unconnected-(X2-Pad1)") (class "Default")
      (node (ref "X2") (pin "1") (pinfunction "1_1") (pintype "passive"))
    )
    (net (code "213") (name "unconnected-(X2AA-1-Pad122)") (class "Default")
      (node (ref "X2") (pin "122") (pinfunction "1_122") (pintype "passive"))
    )
    (net (code "214") (name "unconnected-(X2AB-1-Pad123)") (class "Default")
      (node (ref "X2") (pin "123") (pinfunction "1_123") (pintype "passive"))
    )
    (net (code "215") (name "unconnected-(X2AC-1-Pad124)") (class "Default")
      (node (ref "X2") (pin "124") (pinfunction "1_124") (pintype "passive"))
    )
    (net (code "216") (name "unconnected-(X2AD-1-Pad125)") (class "Default")
      (node (ref "X2") (pin "125") (pinfunction "1_125") (pintype "passive"))
    )
    (net (code "217") (name "unconnected-(X2AE-1-Pad126)") (class "Default")
      (node (ref "X2") (pin "126") (pinfunction "1_126") (pintype "passive"))
    )
    (net (code "218") (name "unconnected-(X2AF-1-Pad127)") (class "Default")
      (node (ref "X2") (pin "127") (pinfunction "1_127") (pintype "passive"))
    )
    (net (code "219") (name "unconnected-(X2AG-1-Pad128)") (class "Default")
      (node (ref "X2") (pin "128") (pinfunction "1_128") (pintype "passive"))
    )
    (net (code "220") (name "unconnected-(X2AH-1-Pad129)") (class "Default")
      (node (ref "X2") (pin "129") (pinfunction "1_129") (pintype "passive"))
    )
    (net (code "221") (name "unconnected-(X2AI-1-Pad13)") (class "Default")
      (node (ref "X2") (pin "13") (pinfunction "1_13") (pintype "passive"))
    )
    (net (code "222") (name "unconnected-(X2AJ-1-Pad130)") (class "Default")
      (node (ref "X2") (pin "130") (pinfunction "1_130") (pintype "passive"))
    )
    (net (code "223") (name "unconnected-(X2AK-1-Pad131)") (class "Default")
      (node (ref "X2") (pin "131") (pinfunction "1_131") (pintype "passive"))
    )
    (net (code "224") (name "unconnected-(X2AL-1-Pad132)") (class "Default")
      (node (ref "X2") (pin "132") (pinfunction "1_132") (pintype "passive"))
    )
    (net (code "225") (name "unconnected-(X2AM-1-Pad133)") (class "Default")
      (node (ref "X2") (pin "133") (pinfunction "1_133") (pintype "passive"))
    )
    (net (code "226") (name "unconnected-(X2AN-1-Pad134)") (class "Default")
      (node (ref "X2") (pin "134") (pinfunction "1_134") (pintype "passive"))
    )
    (net (code "227") (name "unconnected-(X2AO-1-Pad135)") (class "Default")
      (node (ref "X2") (pin "135") (pinfunction "1_135") (pintype "passive"))
    )
    (net (code "228") (name "unconnected-(X2AP-1-Pad136)") (class "Default")
      (node (ref "X2") (pin "136") (pinfunction "1_136") (pintype "passive"))
    )
    (net (code "229") (name "unconnected-(X2AQ-1-Pad137)") (class "Default")
      (node (ref "X2") (pin "137") (pinfunction "1_137") (pintype "passive"))
    )
    (net (code "230") (name "unconnected-(X2AR-1-Pad138)") (class "Default")
      (node (ref "X2") (pin "138") (pinfunction "1_138") (pintype "passive"))
    )
    (net (code "231") (name "unconnected-(X2AS-1-Pad139)") (class "Default")
      (node (ref "X2") (pin "139") (pinfunction "1_139") (pintype "passive"))
    )
    (net (code "232") (name "unconnected-(X2AT-1-Pad14)") (class "Default")
      (node (ref "X2") (pin "14") (pinfunction "1_14") (pintype "passive"))
    )
    (net (code "233") (name "unconnected-(X2AU-1-Pad140)") (class "Default")
      (node (ref "X2") (pin "140") (pinfunction "1_140") (pintype "passive"))
    )
    (net (code "234") (name "unconnected-(X2AV-1-Pad141)") (class "Default")
      (node (ref "X2") (pin "141") (pinfunction "1_141") (pintype "passive"))
    )
    (net (code "235") (name "unconnected-(X2AW-1-Pad142)") (class "Default")
      (node (ref "X2") (pin "142") (pinfunction "1_142") (pintype "passive"))
    )
    (net (code "236") (name "unconnected-(X2AX-1-Pad143)") (class "Default")
      (node (ref "X2") (pin "143") (pinfunction "1_143") (pintype "passive"))
    )
    (net (code "237") (name "unconnected-(X2AY-1-Pad144)") (class "Default")
      (node (ref "X2") (pin "144") (pinfunction "1_144") (pintype "passive"))
    )
    (net (code "238") (name "unconnected-(X2AZ-1-Pad145)") (class "Default")
      (node (ref "X2") (pin "145") (pinfunction "1_145") (pintype "passive"))
    )
    (net (code "239") (name "unconnected-(X2B-1-Pad10)") (class "Default")
      (node (ref "X2") (pin "10") (pinfunction "1_10") (pintype "passive"))
    )
    (net (code "240") (name "unconnected-(X2BA-1-Pad146)") (class "Default")
      (node (ref "X2") (pin "146") (pinfunction "1_146") (pintype "passive"))
    )
    (net (code "241") (name "unconnected-(X2BB-1-Pad147)") (class "Default")
      (node (ref "X2") (pin "147") (pinfunction "1_147") (pintype "passive"))
    )
    (net (code "242") (name "unconnected-(X2BC-1-Pad148)") (class "Default")
      (node (ref "X2") (pin "148") (pinfunction "1_148") (pintype "passive"))
    )
    (net (code "243") (name "unconnected-(X2BD-1-Pad149)") (class "Default")
      (node (ref "X2") (pin "149") (pinfunction "1_149") (pintype "passive"))
    )
    (net (code "244") (name "unconnected-(X2BE-1-Pad15)") (class "Default")
      (node (ref "X2") (pin "15") (pinfunction "1_15") (pintype "passive"))
    )
    (net (code "245") (name "unconnected-(X2BF-1-Pad150)") (class "Default")
      (node (ref "X2") (pin "150") (pinfunction "1_150") (pintype "passive"))
    )
    (net (code "246") (name "unconnected-(X2BG-1-Pad151)") (class "Default")
      (node (ref "X2") (pin "151") (pinfunction "1_151") (pintype "passive"))
    )
    (net (code "247") (name "unconnected-(X2BH-1-Pad152)") (class "Default")
      (node (ref "X2") (pin "152") (pinfunction "1_152") (pintype "passive"))
    )
    (net (code "248") (name "unconnected-(X2BI-1-Pad153)") (class "Default")
      (node (ref "X2") (pin "153") (pinfunction "1_153") (pintype "passive"))
    )
    (net (code "249") (name "unconnected-(X2BJ-1-Pad154)") (class "Default")
      (node (ref "X2") (pin "154") (pinfunction "1_154") (pintype "passive"))
    )
    (net (code "250") (name "unconnected-(X2BK-1-Pad155)") (class "Default")
      (node (ref "X2") (pin "155") (pinfunction "1_155") (pintype "passive"))
    )
    (net (code "251") (name "unconnected-(X2BL-1-Pad156)") (class "Default")
      (node (ref "X2") (pin "156") (pinfunction "1_156") (pintype "passive"))
    )
    (net (code "252") (name "unconnected-(X2BM-1-Pad157)") (class "Default")
      (node (ref "X2") (pin "157") (pinfunction "1_157") (pintype "passive"))
    )
    (net (code "253") (name "unconnected-(X2BN-1-Pad158)") (class "Default")
      (node (ref "X2") (pin "158") (pinfunction "1_158") (pintype "passive"))
    )
    (net (code "254") (name "unconnected-(X2BO-1-Pad159)") (class "Default")
      (node (ref "X2") (pin "159") (pinfunction "1_159") (pintype "passive"))
    )
    (net (code "255") (name "unconnected-(X2BP-1-Pad16)") (class "Default")
      (node (ref "X2") (pin "16") (pinfunction "1_16") (pintype "passive"))
    )
    (net (code "256") (name "unconnected-(X2BQ-1-Pad160)") (class "Default")
      (node (ref "X2") (pin "160") (pinfunction "1_160") (pintype "passive"))
    )
    (net (code "257") (name "unconnected-(X2BR-1-Pad161)") (class "Default")
      (node (ref "X2") (pin "161") (pinfunction "1_161") (pintype "passive"))
    )
    (net (code "258") (name "unconnected-(X2BS-1-Pad162)") (class "Default")
      (node (ref "X2") (pin "162") (pinfunction "1_162") (pintype "passive"))
    )
    (net (code "259") (name "unconnected-(X2BT-1-Pad163)") (class "Default")
      (node (ref "X2") (pin "163") (pinfunction "1_163") (pintype "passive"))
    )
    (net (code "260") (name "unconnected-(X2BU-1-Pad164)") (class "Default")
      (node (ref "X2") (pin "164") (pinfunction "1_164") (pintype "passive"))
    )
    (net (code "261") (name "unconnected-(X2BV-1-Pad165)") (class "Default")
      (node (ref "X2") (pin "165") (pinfunction "1_165") (pintype "passive"))
    )
    (net (code "262") (name "unconnected-(X2BW-1-Pad166)") (class "Default")
      (node (ref "X2") (pin "166") (pinfunction "1_166") (pintype "passive"))
    )
    (net (code "263") (name "unconnected-(X2BX-1-Pad167)") (class "Default")
      (node (ref "X2") (pin "167") (pinfunction "1_167") (pintype "passive"))
    )
    (net (code "264") (name "unconnected-(X2BY-1-Pad168)") (class "Default")
      (node (ref "X2") (pin "168") (pinfunction "1_168") (pintype "passive"))
    )
    (net (code "265") (name "unconnected-(X2BZ-1-Pad169)") (class "Default")
      (node (ref "X2") (pin "169") (pinfunction "1_169") (pintype "passive"))
    )
    (net (code "266") (name "unconnected-(X2C-1-Pad100)") (class "Default")
      (node (ref "X2") (pin "100") (pinfunction "1_100") (pintype "passive"))
    )
    (net (code "267") (name "unconnected-(X2CA-1-Pad17)") (class "Default")
      (node (ref "X2") (pin "17") (pinfunction "1_17") (pintype "passive"))
    )
    (net (code "268") (name "unconnected-(X2CB-1-Pad170)") (class "Default")
      (node (ref "X2") (pin "170") (pinfunction "1_170") (pintype "passive"))
    )
    (net (code "269") (name "unconnected-(X2CC-1-Pad171)") (class "Default")
      (node (ref "X2") (pin "171") (pinfunction "1_171") (pintype "passive"))
    )
    (net (code "270") (name "unconnected-(X2CD-1-Pad172)") (class "Default")
      (node (ref "X2") (pin "172") (pinfunction "1_172") (pintype "passive"))
    )
    (net (code "271") (name "unconnected-(X2CE-1-Pad173)") (class "Default")
      (node (ref "X2") (pin "173") (pinfunction "1_173") (pintype "passive"))
    )
    (net (code "272") (name "unconnected-(X2CF-1-Pad174)") (class "Default")
      (node (ref "X2") (pin "174") (pinfunction "1_174") (pintype "passive"))
    )
    (net (code "273") (name "unconnected-(X2CG-1-Pad175)") (class "Default")
      (node (ref "X2") (pin "175") (pinfunction "1_175") (pintype "passive"))
    )
    (net (code "274") (name "unconnected-(X2CH-1-Pad176)") (class "Default")
      (node (ref "X2") (pin "176") (pinfunction "1_176") (pintype "passive"))
    )
    (net (code "275") (name "unconnected-(X2CI-1-Pad177)") (class "Default")
      (node (ref "X2") (pin "177") (pinfunction "1_177") (pintype "passive"))
    )
    (net (code "276") (name "unconnected-(X2CJ-1-Pad178)") (class "Default")
      (node (ref "X2") (pin "178") (pinfunction "1_178") (pintype "passive"))
    )
    (net (code "277") (name "unconnected-(X2CK-1-Pad179)") (class "Default")
      (node (ref "X2") (pin "179") (pinfunction "1_179") (pintype "passive"))
    )
    (net (code "278") (name "unconnected-(X2CL-1-Pad18)") (class "Default")
      (node (ref "X2") (pin "18") (pinfunction "1_18") (pintype "passive"))
    )
    (net (code "279") (name "unconnected-(X2CM-1-Pad180)") (class "Default")
      (node (ref "X2") (pin "180") (pinfunction "1_180") (pintype "passive"))
    )
    (net (code "280") (name "unconnected-(X2CN-1-Pad181)") (class "Default")
      (node (ref "X2") (pin "181") (pinfunction "1_181") (pintype "passive"))
    )
    (net (code "281") (name "unconnected-(X2CO-1-Pad182)") (class "Default")
      (node (ref "X2") (pin "182") (pinfunction "1_182") (pintype "passive"))
    )
    (net (code "282") (name "unconnected-(X2CP-1-Pad183)") (class "Default")
      (node (ref "X2") (pin "183") (pinfunction "1_183") (pintype "passive"))
    )
    (net (code "283") (name "unconnected-(X2CQ-1-Pad184)") (class "Default")
      (node (ref "X2") (pin "184") (pinfunction "1_184") (pintype "passive"))
    )
    (net (code "284") (name "unconnected-(X2CR-1-Pad185)") (class "Default")
      (node (ref "X2") (pin "185") (pinfunction "1_185") (pintype "passive"))
    )
    (net (code "285") (name "unconnected-(X2CS-1-Pad186)") (class "Default")
      (node (ref "X2") (pin "186") (pinfunction "1_186") (pintype "passive"))
    )
    (net (code "286") (name "unconnected-(X2CT-1-Pad187)") (class "Default")
      (node (ref "X2") (pin "187") (pinfunction "1_187") (pintype "passive"))
    )
    (net (code "287") (name "unconnected-(X2CU-1-Pad188)") (class "Default")
      (node (ref "X2") (pin "188") (pinfunction "1_188") (pintype "passive"))
    )
    (net (code "288") (name "unconnected-(X2CV-1-Pad189)") (class "Default")
      (node (ref "X2") (pin "189") (pinfunction "1_189") (pintype "passive"))
    )
    (net (code "289") (name "unconnected-(X2CW-1-Pad19)") (class "Default")
      (node (ref "X2") (pin "19") (pinfunction "1_19") (pintype "passive"))
    )
    (net (code "290") (name "unconnected-(X2CX-1-Pad190)") (class "Default")
      (node (ref "X2") (pin "190") (pinfunction "1_190") (pintype "passive"))
    )
    (net (code "291") (name "unconnected-(X2CY-1-Pad191)") (class "Default")
      (node (ref "X2") (pin "191") (pinfunction "1_191") (pintype "passive"))
    )
    (net (code "292") (name "unconnected-(X2CZ-1-Pad192)") (class "Default")
      (node (ref "X2") (pin "192") (pinfunction "1_192") (pintype "passive"))
    )
    (net (code "293") (name "unconnected-(X2D-1-Pad101)") (class "Default")
      (node (ref "X2") (pin "101") (pinfunction "1_101") (pintype "passive"))
    )
    (net (code "294") (name "unconnected-(X2DA-1-Pad193)") (class "Default")
      (node (ref "X2") (pin "193") (pinfunction "1_193") (pintype "passive"))
    )
    (net (code "295") (name "unconnected-(X2DB-1-Pad194)") (class "Default")
      (node (ref "X2") (pin "194") (pinfunction "1_194") (pintype "passive"))
    )
    (net (code "296") (name "unconnected-(X2DC-1-Pad195)") (class "Default")
      (node (ref "X2") (pin "195") (pinfunction "1_195") (pintype "passive"))
    )
    (net (code "297") (name "unconnected-(X2DD-1-Pad196)") (class "Default")
      (node (ref "X2") (pin "196") (pinfunction "1_196") (pintype "passive"))
    )
    (net (code "298") (name "unconnected-(X2DE-1-Pad197)") (class "Default")
      (node (ref "X2") (pin "197") (pinfunction "1_197") (pintype "passive"))
    )
    (net (code "299") (name "unconnected-(X2DF-1-Pad198)") (class "Default")
      (node (ref "X2") (pin "198") (pinfunction "1_198") (pintype "passive"))
    )
    (net (code "300") (name "unconnected-(X2DG-1-Pad199)") (class "Default")
      (node (ref "X2") (pin "199") (pinfunction "1_199") (pintype "passive"))
    )
    (net (code "301") (name "unconnected-(X2DH-1-Pad2)") (class "Default")
      (node (ref "X2") (pin "2") (pinfunction "1_2") (pintype "passive"))
    )
    (net (code "302") (name "unconnected-(X2DI-1-Pad20)") (class "Default")
      (node (ref "X2") (pin "20") (pinfunction "1_20") (pintype "passive"))
    )
    (net (code "303") (name "unconnected-(X2DJ-1-Pad200)") (class "Default")
      (node (ref "X2") (pin "200") (pinfunction "1_200") (pintype "passive"))
    )
    (net (code "304") (name "unconnected-(X2DK-1-Pad21)") (class "Default")
      (node (ref "X2") (pin "21") (pinfunction "1_21") (pintype "passive"))
    )
    (net (code "305") (name "unconnected-(X2DL-1-Pad22)") (class "Default")
      (node (ref "X2") (pin "22") (pinfunction "1_22") (pintype "passive"))
    )
    (net (code "306") (name "unconnected-(X2DM-1-Pad23)") (class "Default")
      (node (ref "X2") (pin "23") (pinfunction "1_23") (pintype "passive"))
    )
    (net (code "307") (name "unconnected-(X2DN-1-Pad24)") (class "Default")
      (node (ref "X2") (pin "24") (pinfunction "1_24") (pintype "passive"))
    )
    (net (code "308") (name "unconnected-(X2DO-1-Pad25)") (class "Default")
      (node (ref "X2") (pin "25") (pinfunction "1_25") (pintype "passive"))
    )
    (net (code "309") (name "unconnected-(X2DP-1-Pad26)") (class "Default")
      (node (ref "X2") (pin "26") (pinfunction "1_26") (pintype "passive"))
    )
    (net (code "310") (name "unconnected-(X2DQ-1-Pad27)") (class "Default")
      (node (ref "X2") (pin "27") (pinfunction "1_27") (pintype "passive"))
    )
    (net (code "311") (name "unconnected-(X2DR-1-Pad28)") (class "Default")
      (node (ref "X2") (pin "28") (pinfunction "1_28") (pintype "passive"))
    )
    (net (code "312") (name "unconnected-(X2DS-1-Pad29)") (class "Default")
      (node (ref "X2") (pin "29") (pinfunction "1_29") (pintype "passive"))
    )
    (net (code "313") (name "unconnected-(X2DT-1-Pad3)") (class "Default")
      (node (ref "X2") (pin "3") (pinfunction "1_3") (pintype "passive"))
    )
    (net (code "314") (name "unconnected-(X2DU-1-Pad30)") (class "Default")
      (node (ref "X2") (pin "30") (pinfunction "1_30") (pintype "passive"))
    )
    (net (code "315") (name "unconnected-(X2DV-1-Pad31)") (class "Default")
      (node (ref "X2") (pin "31") (pinfunction "1_31") (pintype "passive"))
    )
    (net (code "316") (name "unconnected-(X2DW-1-Pad32)") (class "Default")
      (node (ref "X2") (pin "32") (pinfunction "1_32") (pintype "passive"))
    )
    (net (code "317") (name "unconnected-(X2DX-1-Pad33)") (class "Default")
      (node (ref "X2") (pin "33") (pinfunction "1_33") (pintype "passive"))
    )
    (net (code "318") (name "unconnected-(X2DY-1-Pad34)") (class "Default")
      (node (ref "X2") (pin "34") (pinfunction "1_34") (pintype "passive"))
    )
    (net (code "319") (name "unconnected-(X2DZ-1-Pad35)") (class "Default")
      (node (ref "X2") (pin "35") (pinfunction "1_35") (pintype "passive"))
    )
    (net (code "320") (name "unconnected-(X2E-1-Pad102)") (class "Default")
      (node (ref "X2") (pin "102") (pinfunction "1_102") (pintype "passive"))
    )
    (net (code "321") (name "unconnected-(X2EA-1-Pad36)") (class "Default")
      (node (ref "X2") (pin "36") (pinfunction "1_36") (pintype "passive"))
    )
    (net (code "322") (name "unconnected-(X2EB-1-Pad37)") (class "Default")
      (node (ref "X2") (pin "37") (pinfunction "1_37") (pintype "passive"))
    )
    (net (code "323") (name "unconnected-(X2EC-1-Pad38)") (class "Default")
      (node (ref "X2") (pin "38") (pinfunction "1_38") (pintype "passive"))
    )
    (net (code "324") (name "unconnected-(X2ED-1-Pad39)") (class "Default")
      (node (ref "X2") (pin "39") (pinfunction "1_39") (pintype "passive"))
    )
    (net (code "325") (name "unconnected-(X2EE-1-Pad4)") (class "Default")
      (node (ref "X2") (pin "4") (pinfunction "1_4") (pintype "passive"))
    )
    (net (code "326") (name "unconnected-(X2EF-1-Pad40)") (class "Default")
      (node (ref "X2") (pin "40") (pinfunction "1_40") (pintype "passive"))
    )
    (net (code "327") (name "unconnected-(X2EG-1-Pad41)") (class "Default")
      (node (ref "X2") (pin "41") (pinfunction "1_41") (pintype "passive"))
    )
    (net (code "328") (name "unconnected-(X2EH-1-Pad42)") (class "Default")
      (node (ref "X2") (pin "42") (pinfunction "1_42") (pintype "passive"))
    )
    (net (code "329") (name "unconnected-(X2EI-1-Pad43)") (class "Default")
      (node (ref "X2") (pin "43") (pinfunction "1_43") (pintype "passive"))
    )
    (net (code "330") (name "unconnected-(X2EJ-1-Pad44)") (class "Default")
      (node (ref "X2") (pin "44") (pinfunction "1_44") (pintype "passive"))
    )
    (net (code "331") (name "unconnected-(X2EK-1-Pad45)") (class "Default")
      (node (ref "X2") (pin "45") (pinfunction "1_45") (pintype "passive"))
    )
    (net (code "332") (name "unconnected-(X2EL-1-Pad46)") (class "Default")
      (node (ref "X2") (pin "46") (pinfunction "1_46") (pintype "passive"))
    )
    (net (code "333") (name "unconnected-(X2EM-1-Pad47)") (class "Default")
      (node (ref "X2") (pin "47") (pinfunction "1_47") (pintype "passive"))
    )
    (net (code "334") (name "unconnected-(X2EN-1-Pad48)") (class "Default")
      (node (ref "X2") (pin "48") (pinfunction "1_48") (pintype "passive"))
    )
    (net (code "335") (name "unconnected-(X2EO-1-Pad49)") (class "Default")
      (node (ref "X2") (pin "49") (pinfunction "1_49") (pintype "passive"))
    )
    (net (code "336") (name "unconnected-(X2EP-1-Pad5)") (class "Default")
      (node (ref "X2") (pin "5") (pinfunction "1_5") (pintype "passive"))
    )
    (net (code "337") (name "unconnected-(X2EQ-1-Pad50)") (class "Default")
      (node (ref "X2") (pin "50") (pinfunction "1_50") (pintype "passive"))
    )
    (net (code "338") (name "unconnected-(X2ER-1-Pad51)") (class "Default")
      (node (ref "X2") (pin "51") (pinfunction "1_51") (pintype "passive"))
    )
    (net (code "339") (name "unconnected-(X2ES-1-Pad52)") (class "Default")
      (node (ref "X2") (pin "52") (pinfunction "1_52") (pintype "passive"))
    )
    (net (code "340") (name "unconnected-(X2ET-1-Pad53)") (class "Default")
      (node (ref "X2") (pin "53") (pinfunction "1_53") (pintype "passive"))
    )
    (net (code "341") (name "unconnected-(X2EU-1-Pad54)") (class "Default")
      (node (ref "X2") (pin "54") (pinfunction "1_54") (pintype "passive"))
    )
    (net (code "342") (name "unconnected-(X2EV-1-Pad55)") (class "Default")
      (node (ref "X2") (pin "55") (pinfunction "1_55") (pintype "passive"))
    )
    (net (code "343") (name "unconnected-(X2EW-1-Pad56)") (class "Default")
      (node (ref "X2") (pin "56") (pinfunction "1_56") (pintype "passive"))
    )
    (net (code "344") (name "unconnected-(X2EX-1-Pad57)") (class "Default")
      (node (ref "X2") (pin "57") (pinfunction "1_57") (pintype "passive"))
    )
    (net (code "345") (name "unconnected-(X2EY-1-Pad58)") (class "Default")
      (node (ref "X2") (pin "58") (pinfunction "1_58") (pintype "passive"))
    )
    (net (code "346") (name "unconnected-(X2EZ-1-Pad59)") (class "Default")
      (node (ref "X2") (pin "59") (pinfunction "1_59") (pintype "passive"))
    )
    (net (code "347") (name "unconnected-(X2F-1-Pad103)") (class "Default")
      (node (ref "X2") (pin "103") (pinfunction "1_103") (pintype "passive"))
    )
    (net (code "348") (name "unconnected-(X2FA-1-Pad6)") (class "Default")
      (node (ref "X2") (pin "6") (pinfunction "1_6") (pintype "passive"))
    )
    (net (code "349") (name "unconnected-(X2FB-1-Pad60)") (class "Default")
      (node (ref "X2") (pin "60") (pinfunction "1_60") (pintype "passive"))
    )
    (net (code "350") (name "unconnected-(X2FC-1-Pad61)") (class "Default")
      (node (ref "X2") (pin "61") (pinfunction "1_61") (pintype "passive"))
    )
    (net (code "351") (name "unconnected-(X2FD-1-Pad62)") (class "Default")
      (node (ref "X2") (pin "62") (pinfunction "1_62") (pintype "passive"))
    )
    (net (code "352") (name "unconnected-(X2FE-1-Pad63)") (class "Default")
      (node (ref "X2") (pin "63") (pinfunction "1_63") (pintype "passive"))
    )
    (net (code "353") (name "unconnected-(X2FF-1-Pad64)") (class "Default")
      (node (ref "X2") (pin "64") (pinfunction "1_64") (pintype "passive"))
    )
    (net (code "354") (name "unconnected-(X2FG-1-Pad65)") (class "Default")
      (node (ref "X2") (pin "65") (pinfunction "1_65") (pintype "passive"))
    )
    (net (code "355") (name "unconnected-(X2FH-1-Pad66)") (class "Default")
      (node (ref "X2") (pin "66") (pinfunction "1_66") (pintype "passive"))
    )
    (net (code "356") (name "unconnected-(X2FI-1-Pad67)") (class "Default")
      (node (ref "X2") (pin "67") (pinfunction "1_67") (pintype "passive"))
    )
    (net (code "357") (name "unconnected-(X2FJ-1-Pad68)") (class "Default")
      (node (ref "X2") (pin "68") (pinfunction "1_68") (pintype "passive"))
    )
    (net (code "358") (name "unconnected-(X2FK-1-Pad69)") (class "Default")
      (node (ref "X2") (pin "69") (pinfunction "1_69") (pintype "passive"))
    )
    (net (code "359") (name "unconnected-(X2FL-1-Pad7)") (class "Default")
      (node (ref "X2") (pin "7") (pinfunction "1_7") (pintype "passive"))
    )
    (net (code "360") (name "unconnected-(X2FM-1-Pad70)") (class "Default")
      (node (ref "X2") (pin "70") (pinfunction "1_70") (pintype "passive"))
    )
    (net (code "361") (name "unconnected-(X2FN-1-Pad71)") (class "Default")
      (node (ref "X2") (pin "71") (pinfunction "1_71") (pintype "passive"))
    )
    (net (code "362") (name "unconnected-(X2FO-1-Pad72)") (class "Default")
      (node (ref "X2") (pin "72") (pinfunction "1_72") (pintype "passive"))
    )
    (net (code "363") (name "unconnected-(X2FP-1-Pad73)") (class "Default")
      (node (ref "X2") (pin "73") (pinfunction "1_73") (pintype "passive"))
    )
    (net (code "364") (name "unconnected-(X2FQ-1-Pad74)") (class "Default")
      (node (ref "X2") (pin "74") (pinfunction "1_74") (pintype "passive"))
    )
    (net (code "365") (name "unconnected-(X2FR-1-Pad75)") (class "Default")
      (node (ref "X2") (pin "75") (pinfunction "1_75") (pintype "passive"))
    )
    (net (code "366") (name "unconnected-(X2FS-1-Pad76)") (class "Default")
      (node (ref "X2") (pin "76") (pinfunction "1_76") (pintype "passive"))
    )
    (net (code "367") (name "unconnected-(X2FT-1-Pad77)") (class "Default")
      (node (ref "X2") (pin "77") (pinfunction "1_77") (pintype "passive"))
    )
    (net (code "368") (name "unconnected-(X2FU-1-Pad78)") (class "Default")
      (node (ref "X2") (pin "78") (pinfunction "1_78") (pintype "passive"))
    )
    (net (code "369") (name "unconnected-(X2FV-1-Pad79)") (class "Default")
      (node (ref "X2") (pin "79") (pinfunction "1_79") (pintype "passive"))
    )
    (net (code "370") (name "unconnected-(X2FW-1-Pad8)") (class "Default")
      (node (ref "X2") (pin "8") (pinfunction "1_8") (pintype "passive"))
    )
    (net (code "371") (name "unconnected-(X2FX-1-Pad80)") (class "Default")
      (node (ref "X2") (pin "80") (pinfunction "1_80") (pintype "passive"))
    )
    (net (code "372") (name "unconnected-(X2FY-1-Pad81)") (class "Default")
      (node (ref "X2") (pin "81") (pinfunction "1_81") (pintype "passive"))
    )
    (net (code "373") (name "unconnected-(X2FZ-1-Pad82)") (class "Default")
      (node (ref "X2") (pin "82") (pinfunction "1_82") (pintype "passive"))
    )
    (net (code "374") (name "unconnected-(X2G-1-Pad104)") (class "Default")
      (node (ref "X2") (pin "104") (pinfunction "1_104") (pintype "passive"))
    )
    (net (code "375") (name "unconnected-(X2GA-1-Pad83)") (class "Default")
      (node (ref "X2") (pin "83") (pinfunction "1_83") (pintype "passive"))
    )
    (net (code "376") (name "unconnected-(X2GB-1-Pad84)") (class "Default")
      (node (ref "X2") (pin "84") (pinfunction "1_84") (pintype "passive"))
    )
    (net (code "377") (name "unconnected-(X2GC-1-Pad85)") (class "Default")
      (node (ref "X2") (pin "85") (pinfunction "1_85") (pintype "passive"))
    )
    (net (code "378") (name "unconnected-(X2GD-1-Pad86)") (class "Default")
      (node (ref "X2") (pin "86") (pinfunction "1_86") (pintype "passive"))
    )
    (net (code "379") (name "unconnected-(X2GE-1-Pad87)") (class "Default")
      (node (ref "X2") (pin "87") (pinfunction "1_87") (pintype "passive"))
    )
    (net (code "380") (name "unconnected-(X2GF-1-Pad88)") (class "Default")
      (node (ref "X2") (pin "88") (pinfunction "1_88") (pintype "passive"))
    )
    (net (code "381") (name "unconnected-(X2GG-1-Pad89)") (class "Default")
      (node (ref "X2") (pin "89") (pinfunction "1_89") (pintype "passive"))
    )
    (net (code "382") (name "unconnected-(X2GH-1-Pad9)") (class "Default")
      (node (ref "X2") (pin "9") (pinfunction "1_9") (pintype "passive"))
    )
    (net (code "383") (name "unconnected-(X2GI-1-Pad90)") (class "Default")
      (node (ref "X2") (pin "90") (pinfunction "1_90") (pintype "passive"))
    )
    (net (code "384") (name "unconnected-(X2GJ-1-Pad91)") (class "Default")
      (node (ref "X2") (pin "91") (pinfunction "1_91") (pintype "passive"))
    )
    (net (code "385") (name "unconnected-(X2GK-1-Pad92)") (class "Default")
      (node (ref "X2") (pin "92") (pinfunction "1_92") (pintype "passive"))
    )
    (net (code "386") (name "unconnected-(X2GL-1-Pad93)") (class "Default")
      (node (ref "X2") (pin "93") (pinfunction "1_93") (pintype "passive"))
    )
    (net (code "387") (name "unconnected-(X2GM-1-Pad94)") (class "Default")
      (node (ref "X2") (pin "94") (pinfunction "1_94") (pintype "passive"))
    )
    (net (code "388") (name "unconnected-(X2GN-1-Pad95)") (class "Default")
      (node (ref "X2") (pin "95") (pinfunction "1_95") (pintype "passive"))
    )
    (net (code "389") (name "unconnected-(X2GO-1-Pad96)") (class "Default")
      (node (ref "X2") (pin "96") (pinfunction "1_96") (pintype "passive"))
    )
    (net (code "390") (name "unconnected-(X2GP-1-Pad97)") (class "Default")
      (node (ref "X2") (pin "97") (pinfunction "1_97") (pintype "passive"))
    )
    (net (code "391") (name "unconnected-(X2GQ-1-Pad98)") (class "Default")
      (node (ref "X2") (pin "98") (pinfunction "1_98") (pintype "passive"))
    )
    (net (code "392") (name "unconnected-(X2GR-1-Pad99)") (class "Default")
      (node (ref "X2") (pin "99") (pinfunction "1_99") (pintype "passive"))
    )
    (net (code "393") (name "unconnected-(X2H-1-Pad105)") (class "Default")
      (node (ref "X2") (pin "105") (pinfunction "1_105") (pintype "passive"))
    )
    (net (code "394") (name "unconnected-(X2I-1-Pad106)") (class "Default")
      (node (ref "X2") (pin "106") (pinfunction "1_106") (pintype "passive"))
    )
    (net (code "395") (name "unconnected-(X2J-1-Pad107)") (class "Default")
      (node (ref "X2") (pin "107") (pinfunction "1_107") (pintype "passive"))
    )
    (net (code "396") (name "unconnected-(X2K-1-Pad108)") (class "Default")
      (node (ref "X2") (pin "108") (pinfunction "1_108") (pintype "passive"))
    )
    (net (code "397") (name "unconnected-(X2L-1-Pad109)") (class "Default")
      (node (ref "X2") (pin "109") (pinfunction "1_109") (pintype "passive"))
    )
    (net (code "398") (name "unconnected-(X2M-1-Pad11)") (class "Default")
      (node (ref "X2") (pin "11") (pinfunction "1_11") (pintype "passive"))
    )
    (net (code "399") (name "unconnected-(X2N-1-Pad110)") (class "Default")
      (node (ref "X2") (pin "110") (pinfunction "1_110") (pintype "passive"))
    )
    (net (code "400") (name "unconnected-(X2O-1-Pad111)") (class "Default")
      (node (ref "X2") (pin "111") (pinfunction "1_111") (pintype "passive"))
    )
    (net (code "401") (name "unconnected-(X2P-1-Pad112)") (class "Default")
      (node (ref "X2") (pin "112") (pinfunction "1_112") (pintype "passive"))
    )
    (net (code "402") (name "unconnected-(X2Q-1-Pad113)") (class "Default")
      (node (ref "X2") (pin "113") (pinfunction "1_113") (pintype "passive"))
    )
    (net (code "403") (name "unconnected-(X2R-1-Pad114)") (class "Default")
      (node (ref "X2") (pin "114") (pinfunction "1_114") (pintype "passive"))
    )
    (net (code "404") (name "unconnected-(X2S-1-Pad115)") (class "Default")
      (node (ref "X2") (pin "115") (pinfunction "1_115") (pintype "passive"))
    )
    (net (code "405") (name "unconnected-(X2T-1-Pad116)") (class "Default")
      (node (ref "X2") (pin "116") (pinfunction "1_116") (pintype "passive"))
    )
    (net (code "406") (name "unconnected-(X2U-1-Pad117)") (class "Default")
      (node (ref "X2") (pin "117") (pinfunction "1_117") (pintype "passive"))
    )
    (net (code "407") (name "unconnected-(X2V-1-Pad118)") (class "Default")
      (node (ref "X2") (pin "118") (pinfunction "1_118") (pintype "passive"))
    )
    (net (code "408") (name "unconnected-(X2W-1-Pad119)") (class "Default")
      (node (ref "X2") (pin "119") (pinfunction "1_119") (pintype "passive"))
    )
    (net (code "409") (name "unconnected-(X2X-1-Pad12)") (class "Default")
      (node (ref "X2") (pin "12") (pinfunction "1_12") (pintype "passive"))
    )
    (net (code "410") (name "unconnected-(X2Y-1-Pad120)") (class "Default")
      (node (ref "X2") (pin "120") (pinfunction "1_120") (pintype "passive"))
    )
    (net (code "411") (name "unconnected-(X2Z-1-Pad121)") (class "Default")
      (node (ref "X2") (pin "121") (pinfunction "1_121") (pintype "passive"))
    )
  )
)
